# Schematic_Band_Pass.net
KiCad netlist of a schematic drawn in Altium Designer
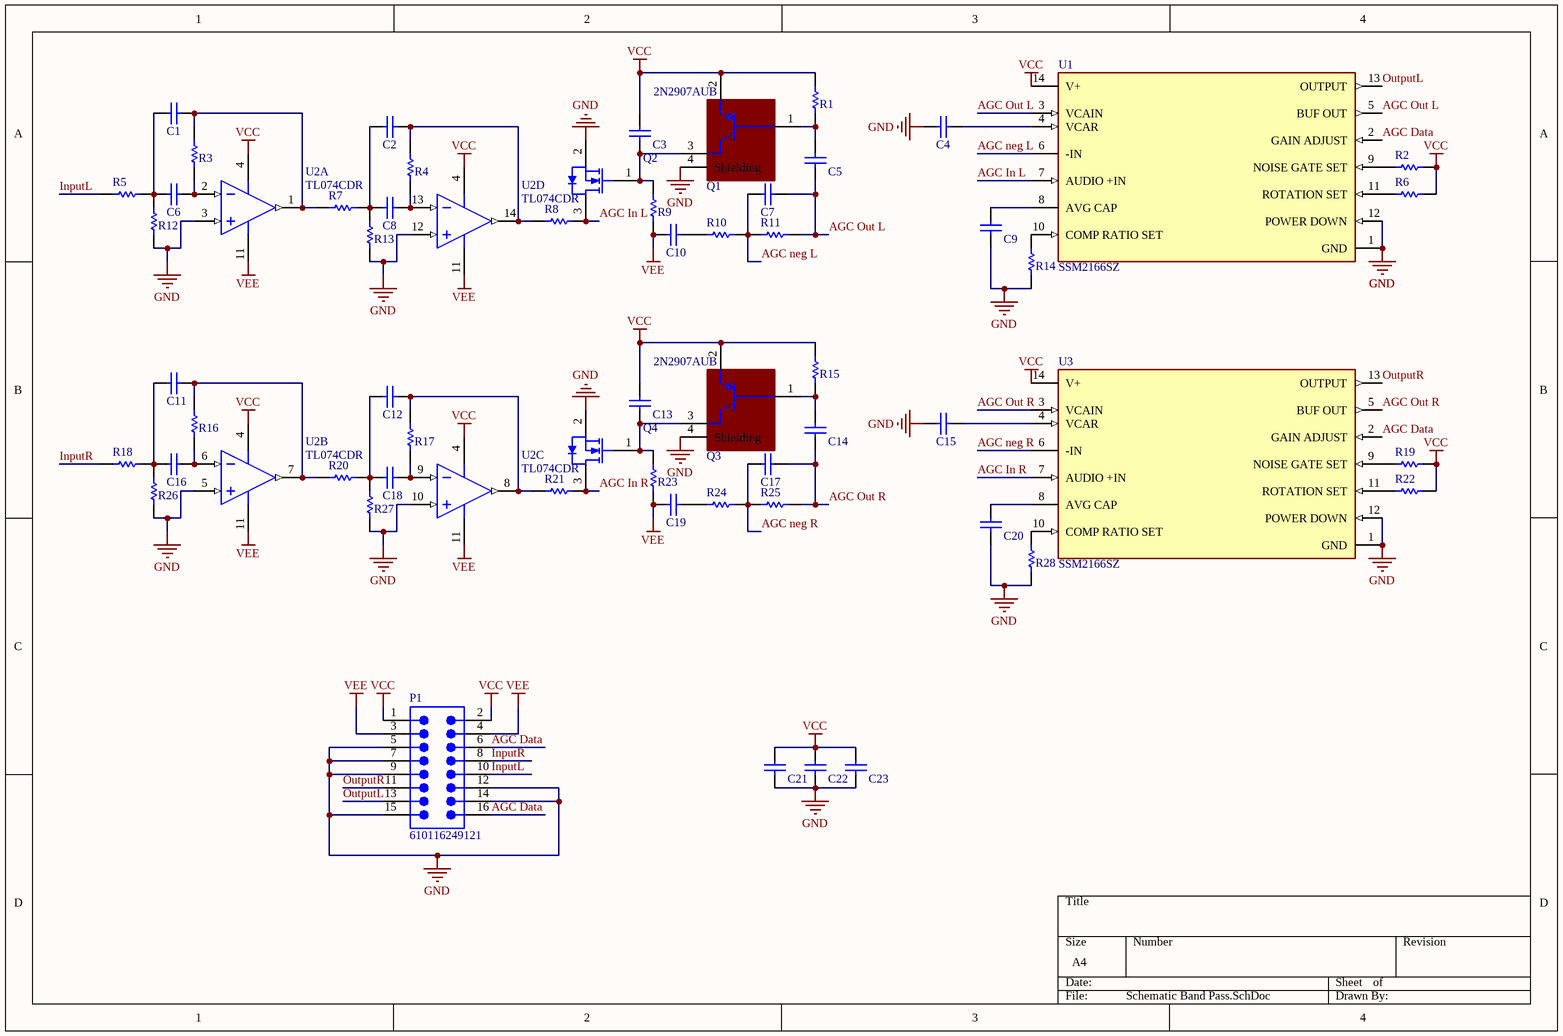
[diagram p0: Schematic Band Pass.SchDoc]

(export (version "E")
  (design (tool "Eeschema 10.0.6"))
  (components
    (comp (ref "C1")
      (value "1206GC102KAT1A")
      (footprint "AVX-1206-2_L")
      (description "Chip Capacitor, 1 nF, +/- 10%, -55 to 125 degC, 1206 (3216 Metric), RoHS, Tape and Reel")
      (fields (field (name "TOLERANCE") "10%") (field (name "MANUFACTURER") "AVX"))
      (libsource (lib "Altium Content Vault") (part "CAP-NP-2"))
    )
    (comp (ref "C2")
      (value "1206GC102KAT1A")
      (footprint "AVX-1206-2_L")
      (description "Chip Capacitor, 1 nF, +/- 10%, -55 to 125 degC, 1206 (3216 Metric), RoHS, Tape and Reel")
      (fields (field (name "TOLERANCE") "10%") (field (name "MANUFACTURER") "AVX"))
      (libsource (lib "Altium Content Vault") (part "CAP-NP-2"))
    )
    (comp (ref "C3")
      (value "1206GC102KAT1A")
      (footprint "AVX-1206-2_L")
      (description "Chip Capacitor, 1 nF, +/- 10%, -55 to 125 degC, 1206 (3216 Metric), RoHS, Tape and Reel")
      (fields (field (name "TOLERANCE") "10%") (field (name "MANUFACTURER") "AVX"))
      (libsource (lib "Altium Content Vault") (part "CAP-NP-2"))
    )
    (comp (ref "C4")
      (value "1206GC102KAT1A")
      (footprint "AVX-1206-2_L")
      (description "Chip Capacitor, 1 nF, +/- 10%, -55 to 125 degC, 1206 (3216 Metric), RoHS, Tape and Reel")
      (fields (field (name "TOLERANCE") "10%") (field (name "MANUFACTURER") "AVX"))
      (libsource (lib "Altium Content Vault") (part "CAP-NP-2"))
    )
    (comp (ref "C5")
      (value "1206GC102KAT1A")
      (footprint "AVX-1206-2_L")
      (description "Chip Capacitor, 1 nF, +/- 10%, -55 to 125 degC, 1206 (3216 Metric), RoHS, Tape and Reel")
      (fields (field (name "TOLERANCE") "10%") (field (name "MANUFACTURER") "AVX"))
      (libsource (lib "Altium Content Vault") (part "CAP-NP-2"))
    )
    (comp (ref "C6")
      (value "1206GC102KAT1A")
      (footprint "AVX-1206-2_L")
      (description "Chip Capacitor, 1 nF, +/- 10%, -55 to 125 degC, 1206 (3216 Metric), RoHS, Tape and Reel")
      (fields (field (name "TOLERANCE") "10%") (field (name "MANUFACTURER") "AVX"))
      (libsource (lib "Altium Content Vault") (part "CAP-NP-2"))
    )
    (comp (ref "C7")
      (value "1206GC102KAT1A")
      (footprint "AVX-1206-2_L")
      (description "Chip Capacitor, 1 nF, +/- 10%, -55 to 125 degC, 1206 (3216 Metric), RoHS, Tape and Reel")
      (fields (field (name "TOLERANCE") "10%") (field (name "MANUFACTURER") "AVX"))
      (libsource (lib "Altium Content Vault") (part "CAP-NP-2"))
    )
    (comp (ref "C8")
      (value "1206GC102KAT1A")
      (footprint "AVX-1206-2_L")
      (description "Chip Capacitor, 1 nF, +/- 10%, -55 to 125 degC, 1206 (3216 Metric), RoHS, Tape and Reel")
      (fields (field (name "TOLERANCE") "10%") (field (name "MANUFACTURER") "AVX"))
      (libsource (lib "Altium Content Vault") (part "CAP-NP-2"))
    )
    (comp (ref "C9")
      (value "1206GC102KAT1A")
      (footprint "AVX-1206-2_L")
      (description "Chip Capacitor, 1 nF, +/- 10%, -55 to 125 degC, 1206 (3216 Metric), RoHS, Tape and Reel")
      (fields (field (name "TOLERANCE") "10%") (field (name "MANUFACTURER") "AVX"))
      (libsource (lib "Altium Content Vault") (part "CAP-NP-2"))
    )
    (comp (ref "C10")
      (value "1206GC102KAT1A")
      (footprint "AVX-1206-2_L")
      (description "Chip Capacitor, 1 nF, +/- 10%, -55 to 125 degC, 1206 (3216 Metric), RoHS, Tape and Reel")
      (fields (field (name "TOLERANCE") "10%") (field (name "MANUFACTURER") "AVX"))
      (libsource (lib "Altium Content Vault") (part "CAP-NP-2"))
    )
    (comp (ref "C11")
      (value "1206GC102KAT1A")
      (footprint "AVX-1206-2_L")
      (description "Chip Capacitor, 1 nF, +/- 10%, -55 to 125 degC, 1206 (3216 Metric), RoHS, Tape and Reel")
      (fields (field (name "TOLERANCE") "10%") (field (name "MANUFACTURER") "AVX"))
      (libsource (lib "Altium Content Vault") (part "CAP-NP-2"))
    )
    (comp (ref "C12")
      (value "1206GC102KAT1A")
      (footprint "AVX-1206-2_L")
      (description "Chip Capacitor, 1 nF, +/- 10%, -55 to 125 degC, 1206 (3216 Metric), RoHS, Tape and Reel")
      (fields (field (name "TOLERANCE") "10%") (field (name "MANUFACTURER") "AVX"))
      (libsource (lib "Altium Content Vault") (part "CAP-NP-2"))
    )
    (comp (ref "C13")
      (value "1206GC102KAT1A")
      (footprint "AVX-1206-2_L")
      (description "Chip Capacitor, 1 nF, +/- 10%, -55 to 125 degC, 1206 (3216 Metric), RoHS, Tape and Reel")
      (fields (field (name "TOLERANCE") "10%") (field (name "MANUFACTURER") "AVX"))
      (libsource (lib "Altium Content Vault") (part "CAP-NP-2"))
    )
    (comp (ref "C14")
      (value "1206GC102KAT1A")
      (footprint "AVX-1206-2_L")
      (description "Chip Capacitor, 1 nF, +/- 10%, -55 to 125 degC, 1206 (3216 Metric), RoHS, Tape and Reel")
      (fields (field (name "TOLERANCE") "10%") (field (name "MANUFACTURER") "AVX"))
      (libsource (lib "Altium Content Vault") (part "CAP-NP-2"))
    )
    (comp (ref "C15")
      (value "1206GC102KAT1A")
      (footprint "AVX-1206-2_L")
      (description "Chip Capacitor, 1 nF, +/- 10%, -55 to 125 degC, 1206 (3216 Metric), RoHS, Tape and Reel")
      (fields (field (name "TOLERANCE") "10%") (field (name "MANUFACTURER") "AVX"))
      (libsource (lib "Altium Content Vault") (part "CAP-NP-2"))
    )
    (comp (ref "C16")
      (value "1206GC102KAT1A")
      (footprint "AVX-1206-2_L")
      (description "Chip Capacitor, 1 nF, +/- 10%, -55 to 125 degC, 1206 (3216 Metric), RoHS, Tape and Reel")
      (fields (field (name "TOLERANCE") "10%") (field (name "MANUFACTURER") "AVX"))
      (libsource (lib "Altium Content Vault") (part "CAP-NP-2"))
    )
    (comp (ref "C17")
      (value "1206GC102KAT1A")
      (footprint "AVX-1206-2_L")
      (description "Chip Capacitor, 1 nF, +/- 10%, -55 to 125 degC, 1206 (3216 Metric), RoHS, Tape and Reel")
      (fields (field (name "TOLERANCE") "10%") (field (name "MANUFACTURER") "AVX"))
      (libsource (lib "Altium Content Vault") (part "CAP-NP-2"))
    )
    (comp (ref "C18")
      (value "1206GC102KAT1A")
      (footprint "AVX-1206-2_L")
      (description "Chip Capacitor, 1 nF, +/- 10%, -55 to 125 degC, 1206 (3216 Metric), RoHS, Tape and Reel")
      (fields (field (name "TOLERANCE") "10%") (field (name "MANUFACTURER") "AVX"))
      (libsource (lib "Altium Content Vault") (part "CAP-NP-2"))
    )
    (comp (ref "C19")
      (value "1206GC102KAT1A")
      (footprint "AVX-1206-2_L")
      (description "Chip Capacitor, 1 nF, +/- 10%, -55 to 125 degC, 1206 (3216 Metric), RoHS, Tape and Reel")
      (fields (field (name "TOLERANCE") "10%") (field (name "MANUFACTURER") "AVX"))
      (libsource (lib "Altium Content Vault") (part "CAP-NP-2"))
    )
    (comp (ref "C20")
      (value "1206GC102KAT1A")
      (footprint "AVX-1206-2_L")
      (description "Chip Capacitor, 1 nF, +/- 10%, -55 to 125 degC, 1206 (3216 Metric), RoHS, Tape and Reel")
      (fields (field (name "TOLERANCE") "10%") (field (name "MANUFACTURER") "AVX"))
      (libsource (lib "Altium Content Vault") (part "CAP-NP-2"))
    )
    (comp (ref "C21")
      (value "1206GC102KAT1A")
      (footprint "AVX-1206-2_L")
      (description "Chip Capacitor, 1 nF, +/- 10%, -55 to 125 degC, 1206 (3216 Metric), RoHS, Tape and Reel")
      (fields (field (name "TOLERANCE") "10%") (field (name "MANUFACTURER") "AVX"))
      (libsource (lib "Altium Content Vault") (part "CAP-NP-2"))
    )
    (comp (ref "C22")
      (value "1206GC102KAT1A")
      (footprint "AVX-1206-2_L")
      (description "Chip Capacitor, 1 nF, +/- 10%, -55 to 125 degC, 1206 (3216 Metric), RoHS, Tape and Reel")
      (fields (field (name "TOLERANCE") "10%") (field (name "MANUFACTURER") "AVX"))
      (libsource (lib "Altium Content Vault") (part "CAP-NP-2"))
    )
    (comp (ref "C23")
      (value "1206GC102KAT1A")
      (footprint "AVX-1206-2_L")
      (description "Chip Capacitor, 1 nF, +/- 10%, -55 to 125 degC, 1206 (3216 Metric), RoHS, Tape and Reel")
      (fields (field (name "TOLERANCE") "10%") (field (name "MANUFACTURER") "AVX"))
      (libsource (lib "Altium Content Vault") (part "CAP-NP-2"))
    )
    (comp (ref "P1")
      (value "610116249121")
      (footprint "610116249121")
      (libsource (lib "Altium Content Vault") (part "Header_Male_2R_16P"))
    )
    (comp (ref "Q1")
      (value "2N2907AUB")
      (footprint "FP-UB-IPC_C")
      (description "TRANS PNP 60V 0.6A")
      (fields
        (field (name "MANUFACTURER") "Microsemi")
        (field (name "OCTOPART") "https://octopart.com/2n2907aub-microsemi-2441590")
      )
      (libsource (lib "Altium Content Vault") (part "db4680ccbeb09cba646b10e5a9b8c77"))
    )
    (comp (ref "Q2")
      (value "2N7002-T1-E3")
      (footprint "VISH-TO-236-3_A_L")
      (description "N-Channel MOSFET, 115 mA, 60 V, -55 to 150 degC, 3-Pin SOT23, RoHS, Tape and Reel")
      (fields (field (name "MANUFACTURER") "Vishay"))
      (libsource (lib "Altium Content Vault") (part "NEMOS-GSD-3"))
    )
    (comp (ref "Q3")
      (value "2N2907AUB")
      (footprint "FP-UB-IPC_C")
      (description "TRANS PNP 60V 0.6A")
      (fields
        (field (name "MANUFACTURER") "Microsemi")
        (field (name "OCTOPART") "https://octopart.com/2n2907aub-microsemi-2441590")
      )
      (libsource (lib "Altium Content Vault") (part "db4680ccbeb09cba646b10e5a9b8c77"))
    )
    (comp (ref "Q4")
      (value "2N7002-T1-E3")
      (footprint "VISH-TO-236-3_A_L")
      (description "N-Channel MOSFET, 115 mA, 60 V, -55 to 150 degC, 3-Pin SOT23, RoHS, Tape and Reel")
      (fields (field (name "MANUFACTURER") "Vishay"))
      (libsource (lib "Altium Content Vault") (part "NEMOS-GSD-3"))
    )
    (comp (ref "R1")
      (value "ERJ-8GEY0R00V")
      (footprint "RESC3216X70X50NL05T20")
      (fields (field (name "MANUFACTURER") "Panasonic"))
      (libsource (lib "Altium Content Vault") (part "RES"))
    )
    (comp (ref "R2")
      (value "ERJ-8GEY0R00V")
      (footprint "RESC3216X70X50NL05T20")
      (fields (field (name "MANUFACTURER") "Panasonic"))
      (libsource (lib "Altium Content Vault") (part "RES"))
    )
    (comp (ref "R3")
      (value "ERJ-8GEY0R00V")
      (footprint "RESC3216X70X50NL05T20")
      (fields (field (name "MANUFACTURER") "Panasonic"))
      (libsource (lib "Altium Content Vault") (part "RES"))
    )
    (comp (ref "R4")
      (value "ERJ-8GEY0R00V")
      (footprint "RESC3216X70X50NL05T20")
      (fields (field (name "MANUFACTURER") "Panasonic"))
      (libsource (lib "Altium Content Vault") (part "RES"))
    )
    (comp (ref "R5")
      (value "ERJ-8GEY0R00V")
      (footprint "RESC3216X70X50NL05T20")
      (fields (field (name "MANUFACTURER") "Panasonic"))
      (libsource (lib "Altium Content Vault") (part "RES"))
    )
    (comp (ref "R6")
      (value "ERJ-8GEY0R00V")
      (footprint "RESC3216X70X50NL05T20")
      (fields (field (name "MANUFACTURER") "Panasonic"))
      (libsource (lib "Altium Content Vault") (part "RES"))
    )
    (comp (ref "R7")
      (value "ERJ-8GEY0R00V")
      (footprint "RESC3216X70X50NL05T20")
      (fields (field (name "MANUFACTURER") "Panasonic"))
      (libsource (lib "Altium Content Vault") (part "RES"))
    )
    (comp (ref "R8")
      (value "ERJ-8GEY0R00V")
      (footprint "RESC3216X70X50NL05T20")
      (fields (field (name "MANUFACTURER") "Panasonic"))
      (libsource (lib "Altium Content Vault") (part "RES"))
    )
    (comp (ref "R9")
      (value "ERJ-8GEY0R00V")
      (footprint "RESC3216X70X50NL05T20")
      (fields (field (name "MANUFACTURER") "Panasonic"))
      (libsource (lib "Altium Content Vault") (part "RES"))
    )
    (comp (ref "R10")
      (value "ERJ-8GEY0R00V")
      (footprint "RESC3216X70X50NL05T20")
      (fields (field (name "MANUFACTURER") "Panasonic"))
      (libsource (lib "Altium Content Vault") (part "RES"))
    )
    (comp (ref "R11")
      (value "ERJ-8GEY0R00V")
      (footprint "RESC3216X70X50NL05T20")
      (fields (field (name "MANUFACTURER") "Panasonic"))
      (libsource (lib "Altium Content Vault") (part "RES"))
    )
    (comp (ref "R12")
      (value "ERJ-8GEY0R00V")
      (footprint "RESC3216X70X50NL05T20")
      (fields (field (name "MANUFACTURER") "Panasonic"))
      (libsource (lib "Altium Content Vault") (part "RES"))
    )
    (comp (ref "R13")
      (value "ERJ-8GEY0R00V")
      (footprint "RESC3216X70X50NL05T20")
      (fields (field (name "MANUFACTURER") "Panasonic"))
      (libsource (lib "Altium Content Vault") (part "RES"))
    )
    (comp (ref "R14")
      (value "ERJ-8GEY0R00V")
      (footprint "RESC3216X70X50NL05T20")
      (fields (field (name "MANUFACTURER") "Panasonic"))
      (libsource (lib "Altium Content Vault") (part "RES"))
    )
    (comp (ref "R15")
      (value "ERJ-8GEY0R00V")
      (footprint "RESC3216X70X50NL05T20")
      (fields (field (name "MANUFACTURER") "Panasonic"))
      (libsource (lib "Altium Content Vault") (part "RES"))
    )
    (comp (ref "R16")
      (value "ERJ-8GEY0R00V")
      (footprint "RESC3216X70X50NL05T20")
      (fields (field (name "MANUFACTURER") "Panasonic"))
      (libsource (lib "Altium Content Vault") (part "RES"))
    )
    (comp (ref "R17")
      (value "ERJ-8GEY0R00V")
      (footprint "RESC3216X70X50NL05T20")
      (fields (field (name "MANUFACTURER") "Panasonic"))
      (libsource (lib "Altium Content Vault") (part "RES"))
    )
    (comp (ref "R18")
      (value "ERJ-8GEY0R00V")
      (footprint "RESC3216X70X50NL05T20")
      (fields (field (name "MANUFACTURER") "Panasonic"))
      (libsource (lib "Altium Content Vault") (part "RES"))
    )
    (comp (ref "R19")
      (value "ERJ-8GEY0R00V")
      (footprint "RESC3216X70X50NL05T20")
      (fields (field (name "MANUFACTURER") "Panasonic"))
      (libsource (lib "Altium Content Vault") (part "RES"))
    )
    (comp (ref "R20")
      (value "ERJ-8GEY0R00V")
      (footprint "RESC3216X70X50NL05T20")
      (fields (field (name "MANUFACTURER") "Panasonic"))
      (libsource (lib "Altium Content Vault") (part "RES"))
    )
    (comp (ref "R21")
      (value "ERJ-8GEY0R00V")
      (footprint "RESC3216X70X50NL05T20")
      (fields (field (name "MANUFACTURER") "Panasonic"))
      (libsource (lib "Altium Content Vault") (part "RES"))
    )
    (comp (ref "R22")
      (value "ERJ-8GEY0R00V")
      (footprint "RESC3216X70X50NL05T20")
      (fields (field (name "MANUFACTURER") "Panasonic"))
      (libsource (lib "Altium Content Vault") (part "RES"))
    )
    (comp (ref "R23")
      (value "ERJ-8GEY0R00V")
      (footprint "RESC3216X70X50NL05T20")
      (fields (field (name "MANUFACTURER") "Panasonic"))
      (libsource (lib "Altium Content Vault") (part "RES"))
    )
    (comp (ref "R24")
      (value "ERJ-8GEY0R00V")
      (footprint "RESC3216X70X50NL05T20")
      (fields (field (name "MANUFACTURER") "Panasonic"))
      (libsource (lib "Altium Content Vault") (part "RES"))
    )
    (comp (ref "R25")
      (value "ERJ-8GEY0R00V")
      (footprint "RESC3216X70X50NL05T20")
      (fields (field (name "MANUFACTURER") "Panasonic"))
      (libsource (lib "Altium Content Vault") (part "RES"))
    )
    (comp (ref "R26")
      (value "ERJ-8GEY0R00V")
      (footprint "RESC3216X70X50NL05T20")
      (fields (field (name "MANUFACTURER") "Panasonic"))
      (libsource (lib "Altium Content Vault") (part "RES"))
    )
    (comp (ref "R27")
      (value "ERJ-8GEY0R00V")
      (footprint "RESC3216X70X50NL05T20")
      (fields (field (name "MANUFACTURER") "Panasonic"))
      (libsource (lib "Altium Content Vault") (part "RES"))
    )
    (comp (ref "R28")
      (value "ERJ-8GEY0R00V")
      (footprint "RESC3216X70X50NL05T20")
      (fields (field (name "MANUFACTURER") "Panasonic"))
      (libsource (lib "Altium Content Vault") (part "RES"))
    )
    (comp (ref "U1")
      (value "SSM2166SZ")
      (footprint "FP-R-14-IPC_C")
      (description "IC AMP CLASS AB MONO 14SOIC")
      (libsource (lib "Altium Content Vault") (part "63c28833aa014cdf51cb94a2eecde41"))
    )
    (comp (ref "U2")
      (value "TL074CDR")
      (footprint "D0014A_N")
      (fields (field (name "MANUFACTURER") "Texas Instruments"))
      (libsource (lib "Altium Content Vault") (part "TI-TLXX4X_MC3403-X14"))
    )
    (comp (ref "U3")
      (value "SSM2166SZ")
      (footprint "FP-R-14-IPC_C")
      (description "IC AMP CLASS AB MONO 14SOIC")
      (libsource (lib "Altium Content Vault") (part "63c28833aa014cdf51cb94a2eecde41"))
    )
  )
  (nets
    (net (code "1") (name "/AGC Data") (class "Default")
      (node (ref "P1") (pin "16") (pinfunction "16_16") (pintype "passive"))
      (node (ref "P1") (pin "6") (pinfunction "6_6") (pintype "passive"))
      (node (ref "U1") (pin "2") (pinfunction "GAIN_ADJUST_2") (pintype "input"))
      (node (ref "U3") (pin "2") (pinfunction "GAIN_ADJUST_2") (pintype "input"))
    )
    (net (code "2") (name "/AGC In L") (class "Default")
      (node (ref "Q2") (pin "3") (pinfunction "D_3") (pintype "passive"))
      (node (ref "R8") (pin "2") (pinfunction "2_2") (pintype "passive"))
      (node (ref "U1") (pin "7") (pinfunction "AUDIO_+IN_7") (pintype "input"))
    )
    (net (code "3") (name "/AGC In R") (class "Default")
      (node (ref "Q4") (pin "3") (pinfunction "D_3") (pintype "passive"))
      (node (ref "R21") (pin "2") (pinfunction "2_2") (pintype "passive"))
      (node (ref "U3") (pin "7") (pinfunction "AUDIO_+IN_7") (pintype "input"))
    )
    (net (code "4") (name "/AGC Out L") (class "Default")
      (node (ref "C5") (pin "2") (pinfunction "2_2") (pintype "passive"))
      (node (ref "C7") (pin "2") (pinfunction "2_2") (pintype "passive"))
      (node (ref "R11") (pin "2") (pinfunction "2_2") (pintype "passive"))
      (node (ref "U1") (pin "3") (pinfunction "VCAIN_3") (pintype "input"))
      (node (ref "U1") (pin "5") (pinfunction "BUF_OUT_5") (pintype "output"))
    )
    (net (code "5") (name "/AGC Out R") (class "Default")
      (node (ref "C14") (pin "2") (pinfunction "2_2") (pintype "passive"))
      (node (ref "C17") (pin "2") (pinfunction "2_2") (pintype "passive"))
      (node (ref "R25") (pin "2") (pinfunction "2_2") (pintype "passive"))
      (node (ref "U3") (pin "3") (pinfunction "VCAIN_3") (pintype "input"))
      (node (ref "U3") (pin "5") (pinfunction "BUF_OUT_5") (pintype "output"))
    )
    (net (code "6") (name "/AGC neg L") (class "Default")
      (node (ref "C7") (pin "1") (pinfunction "1_1") (pintype "passive"))
      (node (ref "R10") (pin "2") (pinfunction "2_2") (pintype "passive"))
      (node (ref "R11") (pin "1") (pinfunction "1_1") (pintype "passive"))
      (node (ref "U1") (pin "6") (pinfunction "-IN_6") (pintype "tri_state"))
    )
    (net (code "7") (name "/AGC neg R") (class "Default")
      (node (ref "C17") (pin "1") (pinfunction "1_1") (pintype "passive"))
      (node (ref "R24") (pin "2") (pinfunction "2_2") (pintype "passive"))
      (node (ref "R25") (pin "1") (pinfunction "1_1") (pintype "passive"))
      (node (ref "U3") (pin "6") (pinfunction "-IN_6") (pintype "tri_state"))
    )
    (net (code "8") (name "/InputL") (class "Default")
      (node (ref "P1") (pin "10") (pinfunction "10_10") (pintype "passive"))
      (node (ref "R5") (pin "1") (pinfunction "1_1") (pintype "passive"))
    )
    (net (code "9") (name "/InputR") (class "Default")
      (node (ref "P1") (pin "8") (pinfunction "8_8") (pintype "passive"))
      (node (ref "R18") (pin "1") (pinfunction "1_1") (pintype "passive"))
    )
    (net (code "10") (name "/OutputL") (class "Default")
      (node (ref "P1") (pin "13") (pinfunction "13_13") (pintype "passive"))
      (node (ref "U1") (pin "13") (pinfunction "OUTPUT_13") (pintype "output"))
    )
    (net (code "11") (name "/OutputR") (class "Default")
      (node (ref "P1") (pin "11") (pinfunction "11_11") (pintype "passive"))
      (node (ref "U3") (pin "13") (pinfunction "OUTPUT_13") (pintype "output"))
    )
    (net (code "12") (name "GND") (class "Default")
      (node (ref "C15") (pin "1") (pinfunction "1_1") (pintype "passive"))
      (node (ref "C20") (pin "1") (pinfunction "1_1") (pintype "passive"))
      (node (ref "C21") (pin "1") (pinfunction "1_1") (pintype "passive"))
      (node (ref "C22") (pin "1") (pinfunction "1_1") (pintype "passive"))
      (node (ref "C23") (pin "1") (pinfunction "1_1") (pintype "passive"))
      (node (ref "C4") (pin "1") (pinfunction "1_1") (pintype "passive"))
      (node (ref "C9") (pin "1") (pinfunction "1_1") (pintype "passive"))
      (node (ref "P1") (pin "12") (pinfunction "12_12") (pintype "passive"))
      (node (ref "P1") (pin "14") (pinfunction "14_14") (pintype "passive"))
      (node (ref "P1") (pin "15") (pinfunction "15_15") (pintype "passive"))
      (node (ref "P1") (pin "5") (pinfunction "5_5") (pintype "passive"))
      (node (ref "P1") (pin "7") (pinfunction "7_7") (pintype "passive"))
      (node (ref "P1") (pin "9") (pinfunction "9_9") (pintype "passive"))
      (node (ref "Q1") (pin "4") (pinfunction "Shielding_4") (pintype "passive"))
      (node (ref "Q2") (pin "2") (pinfunction "S_2") (pintype "passive"))
      (node (ref "Q3") (pin "4") (pinfunction "Shielding_4") (pintype "passive"))
      (node (ref "Q4") (pin "2") (pinfunction "S_2") (pintype "passive"))
      (node (ref "R12") (pin "1") (pinfunction "1_1") (pintype "passive"))
      (node (ref "R13") (pin "1") (pinfunction "1_1") (pintype "passive"))
      (node (ref "R14") (pin "1") (pinfunction "1_1") (pintype "passive"))
      (node (ref "R26") (pin "1") (pinfunction "1_1") (pintype "passive"))
      (node (ref "R27") (pin "1") (pinfunction "1_1") (pintype "passive"))
      (node (ref "R28") (pin "1") (pinfunction "1_1") (pintype "passive"))
      (node (ref "U1") (pin "1") (pinfunction "GND_1") (pintype "power_in"))
      (node (ref "U1") (pin "12") (pinfunction "POWER_DOWN_12") (pintype "input"))
      (node (ref "U2") (pin "10") (pinfunction "IN3+_10") (pintype "input"))
      (node (ref "U2") (pin "12") (pinfunction "IN4+_12") (pintype "input"))
      (node (ref "U2") (pin "3") (pinfunction "IN1+_3") (pintype "input"))
      (node (ref "U2") (pin "5") (pinfunction "IN2+_5") (pintype "input"))
      (node (ref "U3") (pin "1") (pinfunction "GND_1") (pintype "power_in"))
      (node (ref "U3") (pin "12") (pinfunction "POWER_DOWN_12") (pintype "input"))
    )
    (net (code "13") (name "Net-(C1-Pad1)") (class "Default")
      (node (ref "C1") (pin "1") (pinfunction "1_1") (pintype "passive"))
      (node (ref "C6") (pin "1") (pinfunction "1_1") (pintype "passive"))
      (node (ref "R12") (pin "2") (pinfunction "2_2") (pintype "passive"))
      (node (ref "R5") (pin "2") (pinfunction "2_2") (pintype "passive"))
    )
    (net (code "14") (name "Net-(C2-Pad1)") (class "Default")
      (node (ref "C2") (pin "1") (pinfunction "1_1") (pintype "passive"))
      (node (ref "C8") (pin "1") (pinfunction "1_1") (pintype "passive"))
      (node (ref "R13") (pin "2") (pinfunction "2_2") (pintype "passive"))
      (node (ref "R7") (pin "2") (pinfunction "2_2") (pintype "passive"))
    )
    (net (code "15") (name "Net-(C10-Pad2)") (class "Default")
      (node (ref "C10") (pin "2") (pinfunction "2_2") (pintype "passive"))
      (node (ref "R10") (pin "1") (pinfunction "1_1") (pintype "passive"))
    )
    (net (code "16") (name "Net-(C11-Pad1)") (class "Default")
      (node (ref "C11") (pin "1") (pinfunction "1_1") (pintype "passive"))
      (node (ref "C16") (pin "1") (pinfunction "1_1") (pintype "passive"))
      (node (ref "R18") (pin "2") (pinfunction "2_2") (pintype "passive"))
      (node (ref "R26") (pin "2") (pinfunction "2_2") (pintype "passive"))
    )
    (net (code "17") (name "Net-(C12-Pad1)") (class "Default")
      (node (ref "C12") (pin "1") (pinfunction "1_1") (pintype "passive"))
      (node (ref "C18") (pin "1") (pinfunction "1_1") (pintype "passive"))
      (node (ref "R20") (pin "2") (pinfunction "2_2") (pintype "passive"))
      (node (ref "R27") (pin "2") (pinfunction "2_2") (pintype "passive"))
    )
    (net (code "18") (name "Net-(C19-Pad2)") (class "Default")
      (node (ref "C19") (pin "2") (pinfunction "2_2") (pintype "passive"))
      (node (ref "R24") (pin "1") (pinfunction "1_1") (pintype "passive"))
    )
    (net (code "19") (name "Net-(Q1-B)") (class "Default")
      (node (ref "C5") (pin "1") (pinfunction "1_1") (pintype "passive"))
      (node (ref "Q1") (pin "1") (pinfunction "B_1") (pintype "passive"))
      (node (ref "R1") (pin "1") (pinfunction "1_1") (pintype "passive"))
    )
    (net (code "20") (name "Net-(Q1-C)") (class "Default")
      (node (ref "C3") (pin "2") (pinfunction "2_2") (pintype "passive"))
      (node (ref "Q1") (pin "3") (pinfunction "C_3") (pintype "passive"))
      (node (ref "Q2") (pin "1") (pinfunction "G_1") (pintype "passive"))
      (node (ref "R9") (pin "2") (pinfunction "2_2") (pintype "passive"))
    )
    (net (code "21") (name "Net-(Q3-B)") (class "Default")
      (node (ref "C14") (pin "1") (pinfunction "1_1") (pintype "passive"))
      (node (ref "Q3") (pin "1") (pinfunction "B_1") (pintype "passive"))
      (node (ref "R15") (pin "1") (pinfunction "1_1") (pintype "passive"))
    )
    (net (code "22") (name "Net-(Q3-C)") (class "Default")
      (node (ref "C13") (pin "2") (pinfunction "2_2") (pintype "passive"))
      (node (ref "Q3") (pin "3") (pinfunction "C_3") (pintype "passive"))
      (node (ref "Q4") (pin "1") (pinfunction "G_1") (pintype "passive"))
      (node (ref "R23") (pin "2") (pinfunction "2_2") (pintype "passive"))
    )
    (net (code "23") (name "Net-(U1-AVG_CAP)") (class "Default")
      (node (ref "C9") (pin "2") (pinfunction "2_2") (pintype "passive"))
      (node (ref "U1") (pin "8") (pinfunction "AVG_CAP_8") (pintype "passive"))
    )
    (net (code "24") (name "Net-(U1-COMP_RATIO_SET)") (class "Default")
      (node (ref "R14") (pin "2") (pinfunction "2_2") (pintype "passive"))
      (node (ref "U1") (pin "10") (pinfunction "COMP_RATIO_SET_10") (pintype "input"))
    )
    (net (code "25") (name "Net-(U1-NOISE_GATE_SET)") (class "Default")
      (node (ref "R2") (pin "1") (pinfunction "1_1") (pintype "passive"))
      (node (ref "U1") (pin "9") (pinfunction "NOISE_GATE_SET_9") (pintype "input"))
    )
    (net (code "26") (name "Net-(U1-ROTATION_SET)") (class "Default")
      (node (ref "R6") (pin "1") (pinfunction "1_1") (pintype "passive"))
      (node (ref "U1") (pin "11") (pinfunction "ROTATION_SET_11") (pintype "input"))
    )
    (net (code "27") (name "Net-(U1-VCAR)") (class "Default")
      (node (ref "C4") (pin "2") (pinfunction "2_2") (pintype "passive"))
      (node (ref "U1") (pin "4") (pinfunction "VCAR_4") (pintype "input"))
    )
    (net (code "28") (name "Net-(U2A-IN1-)") (class "Default")
      (node (ref "C6") (pin "2") (pinfunction "2_2") (pintype "passive"))
      (node (ref "R3") (pin "1") (pinfunction "1_1") (pintype "passive"))
      (node (ref "U2") (pin "2") (pinfunction "IN1-_2") (pintype "input"))
    )
    (net (code "29") (name "Net-(U2A-OUT1)") (class "Default")
      (node (ref "C1") (pin "2") (pinfunction "2_2") (pintype "passive"))
      (node (ref "R3") (pin "2") (pinfunction "2_2") (pintype "passive"))
      (node (ref "R7") (pin "1") (pinfunction "1_1") (pintype "passive"))
      (node (ref "U2") (pin "1") (pinfunction "OUT1_1") (pintype "output"))
    )
    (net (code "30") (name "Net-(U2B-IN2-)") (class "Default")
      (node (ref "C16") (pin "2") (pinfunction "2_2") (pintype "passive"))
      (node (ref "R16") (pin "1") (pinfunction "1_1") (pintype "passive"))
      (node (ref "U2") (pin "6") (pinfunction "IN2-_6") (pintype "input"))
    )
    (net (code "31") (name "Net-(U2B-OUT2)") (class "Default")
      (node (ref "C11") (pin "2") (pinfunction "2_2") (pintype "passive"))
      (node (ref "R16") (pin "2") (pinfunction "2_2") (pintype "passive"))
      (node (ref "R20") (pin "1") (pinfunction "1_1") (pintype "passive"))
      (node (ref "U2") (pin "7") (pinfunction "OUT2_7") (pintype "output"))
    )
    (net (code "32") (name "Net-(U2C-IN3-)") (class "Default")
      (node (ref "C18") (pin "2") (pinfunction "2_2") (pintype "passive"))
      (node (ref "R17") (pin "1") (pinfunction "1_1") (pintype "passive"))
      (node (ref "U2") (pin "9") (pinfunction "IN3-_9") (pintype "input"))
    )
    (net (code "33") (name "Net-(U2C-OUT3)") (class "Default")
      (node (ref "C12") (pin "2") (pinfunction "2_2") (pintype "passive"))
      (node (ref "R17") (pin "2") (pinfunction "2_2") (pintype "passive"))
      (node (ref "R21") (pin "1") (pinfunction "1_1") (pintype "passive"))
      (node (ref "U2") (pin "8") (pinfunction "OUT3_8") (pintype "output"))
    )
    (net (code "34") (name "Net-(U2D-IN4-)") (class "Default")
      (node (ref "C8") (pin "2") (pinfunction "2_2") (pintype "passive"))
      (node (ref "R4") (pin "1") (pinfunction "1_1") (pintype "passive"))
      (node (ref "U2") (pin "13") (pinfunction "IN4-_13") (pintype "input"))
    )
    (net (code "35") (name "Net-(U2D-OUT4)") (class "Default")
      (node (ref "C2") (pin "2") (pinfunction "2_2") (pintype "passive"))
      (node (ref "R4") (pin "2") (pinfunction "2_2") (pintype "passive"))
      (node (ref "R8") (pin "1") (pinfunction "1_1") (pintype "passive"))
      (node (ref "U2") (pin "14") (pinfunction "OUT4_14") (pintype "output"))
    )
    (net (code "36") (name "Net-(U3-AVG_CAP)") (class "Default")
      (node (ref "C20") (pin "2") (pinfunction "2_2") (pintype "passive"))
      (node (ref "U3") (pin "8") (pinfunction "AVG_CAP_8") (pintype "passive"))
    )
    (net (code "37") (name "Net-(U3-COMP_RATIO_SET)") (class "Default")
      (node (ref "R28") (pin "2") (pinfunction "2_2") (pintype "passive"))
      (node (ref "U3") (pin "10") (pinfunction "COMP_RATIO_SET_10") (pintype "input"))
    )
    (net (code "38") (name "Net-(U3-NOISE_GATE_SET)") (class "Default")
      (node (ref "R19") (pin "1") (pinfunction "1_1") (pintype "passive"))
      (node (ref "U3") (pin "9") (pinfunction "NOISE_GATE_SET_9") (pintype "input"))
    )
    (net (code "39") (name "Net-(U3-ROTATION_SET)") (class "Default")
      (node (ref "R22") (pin "1") (pinfunction "1_1") (pintype "passive"))
      (node (ref "U3") (pin "11") (pinfunction "ROTATION_SET_11") (pintype "input"))
    )
    (net (code "40") (name "Net-(U3-VCAR)") (class "Default")
      (node (ref "C15") (pin "2") (pinfunction "2_2") (pintype "passive"))
      (node (ref "U3") (pin "4") (pinfunction "VCAR_4") (pintype "input"))
    )
    (net (code "41") (name "VCC") (class "Default")
      (node (ref "C13") (pin "1") (pinfunction "1_1") (pintype "passive"))
      (node (ref "C21") (pin "2") (pinfunction "2_2") (pintype "passive"))
      (node (ref "C22") (pin "2") (pinfunction "2_2") (pintype "passive"))
      (node (ref "C23") (pin "2") (pinfunction "2_2") (pintype "passive"))
      (node (ref "C3") (pin "1") (pinfunction "1_1") (pintype "passive"))
      (node (ref "P1") (pin "1") (pinfunction "1_1") (pintype "passive"))
      (node (ref "P1") (pin "2") (pinfunction "2_2") (pintype "passive"))
      (node (ref "Q1") (pin "2") (pinfunction "E_2") (pintype "passive"))
      (node (ref "Q3") (pin "2") (pinfunction "E_2") (pintype "passive"))
      (node (ref "R1") (pin "2") (pinfunction "2_2") (pintype "passive"))
      (node (ref "R15") (pin "2") (pinfunction "2_2") (pintype "passive"))
      (node (ref "R19") (pin "2") (pinfunction "2_2") (pintype "passive"))
      (node (ref "R2") (pin "2") (pinfunction "2_2") (pintype "passive"))
      (node (ref "R22") (pin "2") (pinfunction "2_2") (pintype "passive"))
      (node (ref "R6") (pin "2") (pinfunction "2_2") (pintype "passive"))
      (node (ref "U1") (pin "14") (pinfunction "V+_14") (pintype "power_in"))
      (node (ref "U2") (pin "4") (pinfunction "VCC+_4") (pintype "power_in"))
      (node (ref "U3") (pin "14") (pinfunction "V+_14") (pintype "power_in"))
    )
    (net (code "42") (name "VEE") (class "Default")
      (node (ref "C10") (pin "1") (pinfunction "1_1") (pintype "passive"))
      (node (ref "C19") (pin "1") (pinfunction "1_1") (pintype "passive"))
      (node (ref "P1") (pin "3") (pinfunction "3_3") (pintype "passive"))
      (node (ref "P1") (pin "4") (pinfunction "4_4") (pintype "passive"))
      (node (ref "R23") (pin "1") (pinfunction "1_1") (pintype "passive"))
      (node (ref "R9") (pin "1") (pinfunction "1_1") (pintype "passive"))
      (node (ref "U2") (pin "11") (pinfunction "VCC-_11") (pintype "power_in"))
    )
  )
)
